# audio.net
KiCad netlist of a schematic drawn in Altium Designer
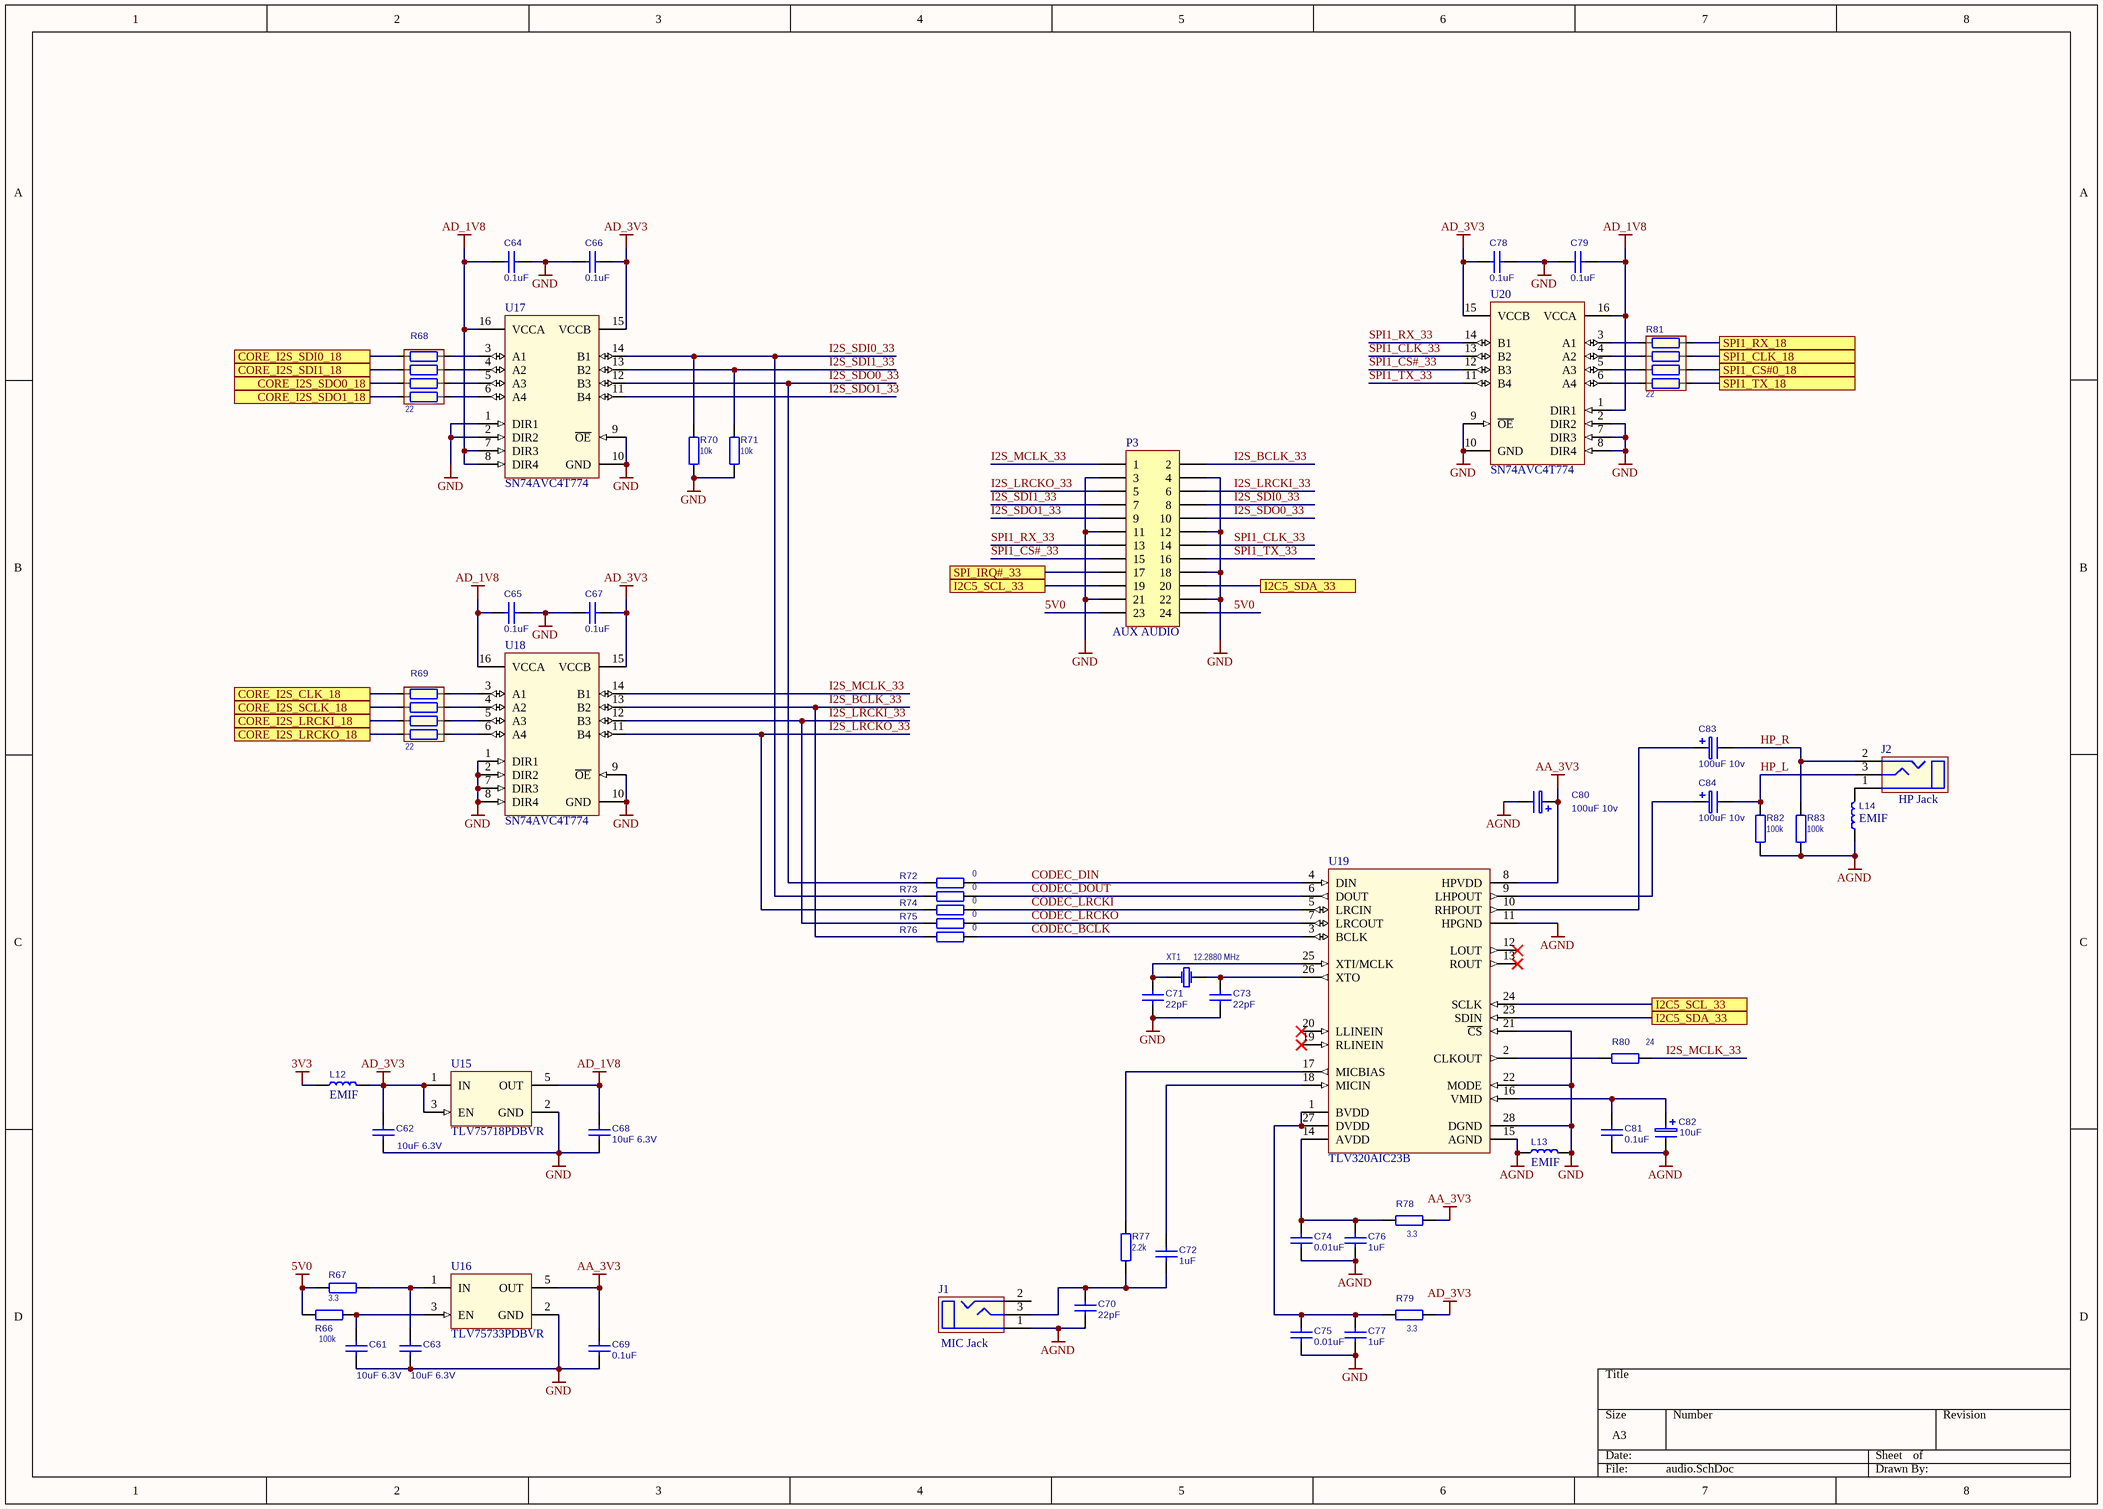
[diagram p0: audio.SchDoc]

(export (version "E")
  (design (tool "Eeschema 10.0.6"))
  (components
    (comp (ref "C61")
      (value "10uF 6.3V")
      (footprint "Capacitors:C0603")
      (description "CAP_NPOL")
      (fields (field (name "Comment") "CC0603MRX5R5BB106"))
      (libsource (lib "capacitors") (part "CAP_NPOL"))
    )
    (comp (ref "C62")
      (value "10uF 6.3V")
      (footprint "Capacitors:C0603")
      (description "CAP_NPOL")
      (fields (field (name "Comment") "CC0603MRX5R5BB106"))
      (libsource (lib "capacitors") (part "CAP_NPOL"))
    )
    (comp (ref "C63")
      (value "10uF 6.3V")
      (footprint "Capacitors:C0603")
      (description "CAP_NPOL")
      (fields (field (name "Comment") "CC0603MRX5R5BB106"))
      (libsource (lib "capacitors") (part "CAP_NPOL"))
    )
    (comp (ref "C64")
      (value "0.1uF")
      (footprint "Capacitors:C0603")
      (description "CAP_NPOL")
      (fields (field (name "Comment") "C1608X7R1H104K080AA"))
      (libsource (lib "capacitors") (part "CAP_NPOL"))
    )
    (comp (ref "C65")
      (value "0.1uF")
      (footprint "Capacitors:C0603")
      (description "CAP_NPOL")
      (fields (field (name "Comment") "C1608X7R1H104K080AA"))
      (libsource (lib "capacitors") (part "CAP_NPOL"))
    )
    (comp (ref "C66")
      (value "0.1uF")
      (footprint "Capacitors:C0603")
      (description "CAP_NPOL")
      (fields (field (name "Comment") "C1608X7R1H104K080AA"))
      (libsource (lib "capacitors") (part "CAP_NPOL"))
    )
    (comp (ref "C67")
      (value "0.1uF")
      (footprint "Capacitors:C0603")
      (description "CAP_NPOL")
      (fields (field (name "Comment") "C1608X7R1H104K080AA"))
      (libsource (lib "capacitors") (part "CAP_NPOL"))
    )
    (comp (ref "C68")
      (value "10uF 6.3V")
      (footprint "Capacitors:C0603")
      (description "CAP_NPOL")
      (fields (field (name "Comment") "CC0603MRX5R5BB106"))
      (libsource (lib "capacitors") (part "CAP_NPOL"))
    )
    (comp (ref "C69")
      (value "0.1uF")
      (footprint "Capacitors:C0603")
      (description "CAP_NPOL")
      (fields (field (name "Comment") "C1608X7R1H104K080AA"))
      (libsource (lib "capacitors") (part "CAP_NPOL"))
    )
    (comp (ref "C70")
      (value "22pF")
      (footprint "C0603")
      (description "CAP_NPOL")
      (libsource (lib "capacitors") (part "CAP_NPOL"))
    )
    (comp (ref "C71")
      (value "22pF")
      (footprint "Capacitors:C0603")
      (description "CAP_NPOL")
      (libsource (lib "capacitors") (part "CAP_NPOL"))
    )
    (comp (ref "C72")
      (value "1uF")
      (footprint "Capacitors:C0603")
      (description "CAP_NPOL")
      (fields (field (name "Comment") "GRM188R61H105KAALD"))
      (libsource (lib "capacitors") (part "CAP_NPOL"))
    )
    (comp (ref "C73")
      (value "22pF")
      (footprint "Capacitors:C0603")
      (description "CAP_NPOL")
      (libsource (lib "capacitors") (part "CAP_NPOL"))
    )
    (comp (ref "C74")
      (value "0.01uF")
      (footprint "Capacitors:C0603")
      (description "CAP_NPOL")
      (fields (field (name "Comment") "C1608X7R1H104K080AA"))
      (libsource (lib "capacitors") (part "CAP_NPOL"))
    )
    (comp (ref "C75")
      (value "0.01uF")
      (footprint "Capacitors:C0603")
      (description "CAP_NPOL")
      (fields (field (name "Comment") "C1608X7R1H104K080AA"))
      (libsource (lib "capacitors") (part "CAP_NPOL"))
    )
    (comp (ref "C76")
      (value "1uF")
      (footprint "Capacitors:C0603")
      (description "CAP_NPOL")
      (fields (field (name "Comment") "GRM188R61H105KAALD"))
      (libsource (lib "capacitors") (part "CAP_NPOL"))
    )
    (comp (ref "C77")
      (value "1uF")
      (footprint "Capacitors:C0603")
      (description "CAP_NPOL")
      (fields (field (name "Comment") "GRM188R61H105KAALD"))
      (libsource (lib "capacitors") (part "CAP_NPOL"))
    )
    (comp (ref "C78")
      (value "0.1uF")
      (footprint "Capacitors:C0603")
      (description "CAP_NPOL")
      (fields (field (name "Comment") "C1608X7R1H104K080AA"))
      (libsource (lib "capacitors") (part "CAP_NPOL"))
    )
    (comp (ref "C79")
      (value "0.1uF")
      (footprint "Capacitors:C0603")
      (description "CAP_NPOL")
      (fields (field (name "Comment") "C1608X7R1H104K080AA"))
      (libsource (lib "capacitors") (part "CAP_NPOL"))
    )
    (comp (ref "C80")
      (value "100uF 10v")
      (footprint "Capacitors:R06H11")
      (description "CAP_POL")
      (fields (field (name "Comment") "SH010M0100B2F-0511"))
      (libsource (lib "capacitors") (part "CAP_POL"))
    )
    (comp (ref "C81")
      (value "0.1uF")
      (footprint "Capacitors:C0603")
      (description "CAP_NPOL")
      (fields (field (name "Comment") "C1608X7R1H104K080AA"))
      (libsource (lib "capacitors") (part "CAP_NPOL"))
    )
    (comp (ref "C82")
      (value "10uF")
      (footprint "Capacitors:TANTAL-A-1206")
      (description "CAP_POL")
      (libsource (lib "capacitors") (part "CAP_POL"))
    )
    (comp (ref "C83")
      (value "100uF 10v")
      (footprint "Capacitors:R06H11")
      (description "CAP_POL")
      (fields (field (name "Comment") "SH010M0100B2F-0511"))
      (libsource (lib "capacitors") (part "CAP_POL"))
    )
    (comp (ref "C84")
      (value "100uF 10v")
      (footprint "Capacitors:R06H11")
      (description "CAP_POL")
      (fields (field (name "Comment") "SH010M0100B2F-0511"))
      (libsource (lib "capacitors") (part "CAP_POL"))
    )
    (comp (ref "J1")
      (value "MIC Jack")
      (footprint "AUB-13")
      (description "Phonejack Stereo")
      (fields (field (name "Comment") "AUB-13"))
      (libsource (lib "PhoneJack") (part "PhoneJackStereo"))
    )
    (comp (ref "J2")
      (value "HP Jack")
      (footprint "AUB-13")
      (description "Phonejack Stereo")
      (fields (field (name "Comment") "AUB-13"))
      (libsource (lib "") (part "PhoneJackStereo_1"))
    )
    (comp (ref "L12")
      (value "EMIF")
      (footprint "IND0805")
      (description "IND_WO_IRON")
      (fields (field (name "Comment") "BLM21PG221SN1D"))
      (libsource (lib "inductors") (part "IND_WO_IRON"))
    )
    (comp (ref "L13")
      (value "EMIF")
      (footprint "IND0805")
      (description "IND_WO_IRON")
      (fields (field (name "Comment") "BLM21PG221SN1D"))
      (libsource (lib "inductors") (part "IND_WO_IRON"))
    )
    (comp (ref "L14")
      (value "EMIF")
      (footprint "IND0805")
      (description "IND_WO_IRON")
      (fields (field (name "Comment") "BLM21PG221SN1D"))
      (libsource (lib "inductors") (part "IND_WO_IRON"))
    )
    (comp (ref "P3")
      (value "AUX AUDIO")
      (footprint "PLD-12")
      (description "Header, 12-Pin, Dual row")
      (fields (field (name "PUBLISHER") "Altium Limited"))
      (libsource (lib "HDR") (part "HDR 12X2"))
    )
    (comp (ref "R66")
      (value "100k")
      (footprint "R0603")
      (description "RES")
      (libsource (lib "resistors") (part "RESISTOR"))
    )
    (comp (ref "R67")
      (value "3.3")
      (footprint "R1206")
      (description "RES")
      (libsource (lib "resistors") (part "RESISTOR"))
    )
    (comp (ref "R68")
      (value "22")
      (footprint "Resistors:R0804X4")
      (description "ARRAY")
      (fields (field (name "Comment") "TC124-JR-0722RL"))
      (libsource (lib "resistors") (part "ARRAY"))
    )
    (comp (ref "R69")
      (value "22")
      (footprint "Resistors:R0804X4")
      (description "ARRAY")
      (fields (field (name "Comment") "TC124-JR-0722RL"))
      (libsource (lib "resistors") (part "ARRAY"))
    )
    (comp (ref "R70")
      (value "10k")
      (footprint "R0603")
      (description "RES")
      (libsource (lib "resistors") (part "RESISTOR"))
    )
    (comp (ref "R71")
      (value "10k")
      (footprint "R0603")
      (description "RES")
      (libsource (lib "resistors") (part "RESISTOR"))
    )
    (comp (ref "R72")
      (value "0")
      (footprint "R0603")
      (description "RES")
      (libsource (lib "resistors") (part "RESISTOR"))
    )
    (comp (ref "R73")
      (value "0")
      (footprint "R0603")
      (description "RES")
      (libsource (lib "resistors") (part "RESISTOR"))
    )
    (comp (ref "R74")
      (value "0")
      (footprint "R0603")
      (description "RES")
      (libsource (lib "resistors") (part "RESISTOR"))
    )
    (comp (ref "R75")
      (value "0")
      (footprint "R0603")
      (description "RES")
      (libsource (lib "resistors") (part "RESISTOR"))
    )
    (comp (ref "R76")
      (value "0")
      (footprint "R0603")
      (description "RES")
      (libsource (lib "resistors") (part "RESISTOR"))
    )
    (comp (ref "R77")
      (value "2.2k")
      (footprint "R0603")
      (description "RES")
      (libsource (lib "resistors") (part "RESISTOR"))
    )
    (comp (ref "R78")
      (value "3.3")
      (footprint "R1206")
      (description "RES")
      (libsource (lib "resistors") (part "RESISTOR"))
    )
    (comp (ref "R79")
      (value "3.3")
      (footprint "R1206")
      (description "RES")
      (libsource (lib "resistors") (part "RESISTOR"))
    )
    (comp (ref "R80")
      (value "24")
      (footprint "R0603")
      (description "RES")
      (fields (field (name "Comment") "22"))
      (libsource (lib "resistors") (part "RESISTOR"))
    )
    (comp (ref "R81")
      (value "22")
      (footprint "Resistors:R0804X4")
      (description "ARRAY")
      (fields (field (name "Comment") "TC124-JR-0722RL"))
      (libsource (lib "") (part "ARRAY_1"))
    )
    (comp (ref "R82")
      (value "100k")
      (footprint "R0603")
      (description "RES")
      (libsource (lib "resistors") (part "RESISTOR"))
    )
    (comp (ref "R83")
      (value "100k")
      (footprint "R0603")
      (description "RES")
      (libsource (lib "resistors") (part "RESISTOR"))
    )
    (comp (ref "U15")
      (value "TLV75718PDBVR")
      (footprint "SOT-23-5")
      (description "Capacitor-Free, 300-mA, Low-Dropout Regulator with Foldback Current Limit for Portable Devices")
      (libsource (lib "TLV733P") (part "TLV733P"))
    )
    (comp (ref "U16")
      (value "TLV75733PDBVR")
      (footprint "SOT-23-5")
      (description "Capacitor-Free, 300-mA, Low-Dropout Regulator with Foldback Current Limit for Portable Devices")
      (libsource (lib "TLV733P") (part "TLV733P"))
    )
    (comp (ref "U17")
      (value "SN74AVC4T774")
      (footprint "TSSOP-16")
      (description "4-Bit Dual-Supply Bus Transceiver With Configurable Voltage-Level Shifting and 3-State Outputs")
      (libsource (lib "SN74AVC4T774") (part "SN74AVC4T774"))
    )
    (comp (ref "U18")
      (value "SN74AVC4T774")
      (footprint "TSSOP-16")
      (description "4-Bit Dual-Supply Bus Transceiver With Configurable Voltage-Level Shifting and 3-State Outputs")
      (libsource (lib "SN74AVC4T774") (part "SN74AVC4T774"))
    )
    (comp (ref "U19")
      (value "TLV320AIC23B")
      (footprint "TSSOP-28")
      (description "Stereo Audio CODEC")
      (libsource (lib "TLV320AIC23") (part "TLV320AIC23"))
    )
    (comp (ref "U20")
      (value "SN74AVC4T774")
      (footprint "TSSOP-16")
      (description "4-Bit Dual-Supply Bus Transceiver With Configurable Voltage-Level Shifting and 3-State Outputs")
      (libsource (lib "") (part "SN74AVC4T774_1"))
    )
    (comp (ref "XT1")
      (value "12.2880 MHz")
      (footprint "HC-49/S")
      (description "Xtal")
      (fields (field (name "Comment") "KX-3H 12.2880 MHz"))
      (libsource (lib "xtal") (part "XTAL"))
    )
  )
  (nets
    (net (code "1") (name "/CODEC_BCLK") (class "Default")
      (node (ref "R76") (pin "2") (pinfunction "2_2") (pintype "passive"))
      (node (ref "U19") (pin "3") (pinfunction "BCLK_3") (pintype "bidirectional"))
    )
    (net (code "2") (name "/CODEC_DIN") (class "Default")
      (node (ref "R72") (pin "2") (pinfunction "2_2") (pintype "passive"))
      (node (ref "U19") (pin "4") (pinfunction "DIN_4") (pintype "input"))
    )
    (net (code "3") (name "/CODEC_DOUT") (class "Default")
      (node (ref "R73") (pin "2") (pinfunction "2_2") (pintype "passive"))
      (node (ref "U19") (pin "6") (pinfunction "DOUT_6") (pintype "output"))
    )
    (net (code "4") (name "/CODEC_LRCKI") (class "Default")
      (node (ref "R74") (pin "2") (pinfunction "2_2") (pintype "passive"))
      (node (ref "U19") (pin "5") (pinfunction "LRCIN_5") (pintype "bidirectional"))
    )
    (net (code "5") (name "/CODEC_LRCKO") (class "Default")
      (node (ref "R75") (pin "2") (pinfunction "2_2") (pintype "passive"))
      (node (ref "U19") (pin "7") (pinfunction "LRCOUT_7") (pintype "bidirectional"))
    )
    (net (code "6") (name "/CORE_I2S_CLK_18") (class "Default")
      (node (ref "R69") (pin "1") (pinfunction "1_1") (pintype "passive"))
    )
    (net (code "7") (name "/CORE_I2S_LRCKI_18") (class "Default")
      (node (ref "R69") (pin "5") (pinfunction "5_5") (pintype "passive"))
    )
    (net (code "8") (name "/CORE_I2S_LRCKO_18") (class "Default")
      (node (ref "R69") (pin "7") (pinfunction "7_7") (pintype "passive"))
    )
    (net (code "9") (name "/CORE_I2S_SCLK_18") (class "Default")
      (node (ref "R69") (pin "3") (pinfunction "3_3") (pintype "passive"))
    )
    (net (code "10") (name "/CORE_I2S_SDI0_18") (class "Default")
      (node (ref "R68") (pin "1") (pinfunction "1_1") (pintype "passive"))
    )
    (net (code "11") (name "/CORE_I2S_SDI1_18") (class "Default")
      (node (ref "R68") (pin "3") (pinfunction "3_3") (pintype "passive"))
    )
    (net (code "12") (name "/CORE_I2S_SDO0_18") (class "Default")
      (node (ref "R68") (pin "5") (pinfunction "5_5") (pintype "passive"))
    )
    (net (code "13") (name "/CORE_I2S_SDO1_18") (class "Default")
      (node (ref "R68") (pin "7") (pinfunction "7_7") (pintype "passive"))
    )
    (net (code "14") (name "/HP_L") (class "Default")
      (node (ref "C84") (pin "2") (pinfunction "-_2") (pintype "passive"))
      (node (ref "J2") (pin "3") (pinfunction "L_3") (pintype "passive"))
      (node (ref "R82") (pin "1") (pinfunction "1_1") (pintype "passive"))
    )
    (net (code "15") (name "/HP_R") (class "Default")
      (node (ref "C83") (pin "2") (pinfunction "-_2") (pintype "passive"))
      (node (ref "J2") (pin "2") (pinfunction "R_2") (pintype "passive"))
      (node (ref "R83") (pin "1") (pinfunction "1_1") (pintype "passive"))
    )
    (net (code "16") (name "/I2C5_SCL_33") (class "Default")
      (node (ref "P3") (pin "19") (pinfunction "19_19") (pintype "passive"))
      (node (ref "U19") (pin "24") (pinfunction "SCLK_24") (pintype "input"))
    )
    (net (code "17") (name "/I2C5_SDA_33") (class "Default")
      (node (ref "P3") (pin "20") (pinfunction "20_20") (pintype "passive"))
      (node (ref "U19") (pin "23") (pinfunction "SDIN_23") (pintype "input"))
    )
    (net (code "18") (name "/I2S_BCLK_33") (class "Default")
      (node (ref "P3") (pin "2") (pinfunction "2_2") (pintype "passive"))
      (node (ref "R76") (pin "1") (pinfunction "1_1") (pintype "passive"))
      (node (ref "U18") (pin "13") (pinfunction "B2_13") (pintype "bidirectional"))
    )
    (net (code "19") (name "/I2S_LRCKI_33") (class "Default")
      (node (ref "P3") (pin "6") (pinfunction "6_6") (pintype "passive"))
      (node (ref "R75") (pin "1") (pinfunction "1_1") (pintype "passive"))
      (node (ref "U18") (pin "12") (pinfunction "B3_12") (pintype "bidirectional"))
    )
    (net (code "20") (name "/I2S_LRCKO_33") (class "Default")
      (node (ref "P3") (pin "5") (pinfunction "5_5") (pintype "passive"))
      (node (ref "R74") (pin "1") (pinfunction "1_1") (pintype "passive"))
      (node (ref "U18") (pin "11") (pinfunction "B4_11") (pintype "bidirectional"))
    )
    (net (code "21") (name "/I2S_MCLK_33") (class "Default")
      (node (ref "P3") (pin "1") (pinfunction "1_1") (pintype "passive"))
      (node (ref "R80") (pin "1") (pinfunction "1_1") (pintype "passive"))
      (node (ref "U18") (pin "14") (pinfunction "B1_14") (pintype "bidirectional"))
    )
    (net (code "22") (name "/I2S_SDI0_33") (class "Default")
      (node (ref "P3") (pin "8") (pinfunction "8_8") (pintype "passive"))
      (node (ref "R70") (pin "1") (pinfunction "1_1") (pintype "passive"))
      (node (ref "R73") (pin "1") (pinfunction "1_1") (pintype "passive"))
      (node (ref "U17") (pin "14") (pinfunction "B1_14") (pintype "bidirectional"))
    )
    (net (code "23") (name "/I2S_SDI1_33") (class "Default")
      (node (ref "P3") (pin "7") (pinfunction "7_7") (pintype "passive"))
      (node (ref "R71") (pin "1") (pinfunction "1_1") (pintype "passive"))
      (node (ref "U17") (pin "13") (pinfunction "B2_13") (pintype "bidirectional"))
    )
    (net (code "24") (name "/I2S_SDO0_33") (class "Default")
      (node (ref "P3") (pin "10") (pinfunction "10_10") (pintype "passive"))
      (node (ref "R72") (pin "1") (pinfunction "1_1") (pintype "passive"))
      (node (ref "U17") (pin "12") (pinfunction "B3_12") (pintype "bidirectional"))
    )
    (net (code "25") (name "/I2S_SDO1_33") (class "Default")
      (node (ref "P3") (pin "9") (pinfunction "9_9") (pintype "passive"))
      (node (ref "U17") (pin "11") (pinfunction "B4_11") (pintype "bidirectional"))
    )
    (net (code "26") (name "/SPI1_CLK_18") (class "Default")
      (node (ref "R81") (pin "3") (pinfunction "3_3") (pintype "passive"))
    )
    (net (code "27") (name "/SPI1_CLK_33") (class "Default")
      (node (ref "P3") (pin "14") (pinfunction "14_14") (pintype "passive"))
      (node (ref "U20") (pin "13") (pinfunction "B2_13") (pintype "bidirectional"))
    )
    (net (code "28") (name "/SPI1_CS#0_18") (class "Default")
      (node (ref "R81") (pin "5") (pinfunction "5_5") (pintype "passive"))
    )
    (net (code "29") (name "/SPI1_CS#_33") (class "Default")
      (node (ref "P3") (pin "15") (pinfunction "15_15") (pintype "passive"))
      (node (ref "U20") (pin "12") (pinfunction "B3_12") (pintype "bidirectional"))
    )
    (net (code "30") (name "/SPI1_RX_18") (class "Default")
      (node (ref "R81") (pin "1") (pinfunction "1_1") (pintype "passive"))
    )
    (net (code "31") (name "/SPI1_RX_33") (class "Default")
      (node (ref "P3") (pin "13") (pinfunction "13_13") (pintype "passive"))
      (node (ref "U20") (pin "14") (pinfunction "B1_14") (pintype "bidirectional"))
    )
    (net (code "32") (name "/SPI1_TX_18") (class "Default")
      (node (ref "R81") (pin "7") (pinfunction "7_7") (pintype "passive"))
    )
    (net (code "33") (name "/SPI1_TX_33") (class "Default")
      (node (ref "P3") (pin "16") (pinfunction "16_16") (pintype "passive"))
      (node (ref "U20") (pin "11") (pinfunction "B4_11") (pintype "bidirectional"))
    )
    (net (code "34") (name "/SPI_IRQ#_33") (class "Default")
      (node (ref "P3") (pin "17") (pinfunction "17_17") (pintype "passive"))
    )
    (net (code "35") (name "3V3") (class "Default") (node (ref "L12") (pin "2") (pintype "passive")))
    (net (code "36") (name "5V0") (class "Default")
      (node (ref "P3") (pin "23") (pinfunction "23_23") (pintype "passive"))
      (node (ref "P3") (pin "24") (pinfunction "24_24") (pintype "passive"))
      (node (ref "R66") (pin "1") (pinfunction "1_1") (pintype "passive"))
      (node (ref "R67") (pin "2") (pinfunction "2_2") (pintype "passive"))
    )
    (net (code "37") (name "AA_3V3") (class "Default")
      (node (ref "C69") (pin "1") (pinfunction "1_1") (pintype "passive"))
      (node (ref "C80") (pin "1") (pinfunction "+_1") (pintype "passive"))
      (node (ref "R78") (pin "1") (pinfunction "1_1") (pintype "passive"))
      (node (ref "U16") (pin "5") (pinfunction "OUT_5") (pintype "power_in"))
      (node (ref "U19") (pin "8") (pinfunction "HPVDD_8") (pintype "power_in"))
    )
    (net (code "38") (name "AD_1V8") (class "Default")
      (node (ref "C64") (pin "2") (pinfunction "2_2") (pintype "passive"))
      (node (ref "C65") (pin "2") (pinfunction "2_2") (pintype "passive"))
      (node (ref "C68") (pin "1") (pinfunction "1_1") (pintype "passive"))
      (node (ref "C79") (pin "2") (pinfunction "2_2") (pintype "passive"))
      (node (ref "U15") (pin "5") (pinfunction "OUT_5") (pintype "power_in"))
      (node (ref "U17") (pin "16") (pinfunction "VCCA_16") (pintype "power_in"))
      (node (ref "U17") (pin "7") (pinfunction "DIR3_7") (pintype "input"))
      (node (ref "U17") (pin "8") (pinfunction "DIR4_8") (pintype "input"))
      (node (ref "U18") (pin "16") (pinfunction "VCCA_16") (pintype "power_in"))
      (node (ref "U20") (pin "1") (pinfunction "DIR1_1") (pintype "input"))
      (node (ref "U20") (pin "16") (pinfunction "VCCA_16") (pintype "power_in"))
    )
    (net (code "39") (name "AD_3V3") (class "Default")
      (node (ref "C62") (pin "1") (pinfunction "1_1") (pintype "passive"))
      (node (ref "C66") (pin "1") (pinfunction "1_1") (pintype "passive"))
      (node (ref "C67") (pin "1") (pinfunction "1_1") (pintype "passive"))
      (node (ref "C78") (pin "1") (pinfunction "1_1") (pintype "passive"))
      (node (ref "L12") (pin "1") (pintype "passive"))
      (node (ref "R79") (pin "1") (pinfunction "1_1") (pintype "passive"))
      (node (ref "U15") (pin "1") (pinfunction "IN_1") (pintype "power_in"))
      (node (ref "U15") (pin "3") (pinfunction "EN_3") (pintype "input"))
      (node (ref "U17") (pin "15") (pinfunction "VCCB_15") (pintype "power_in"))
      (node (ref "U18") (pin "15") (pinfunction "VCCB_15") (pintype "power_in"))
      (node (ref "U20") (pin "15") (pinfunction "VCCB_15") (pintype "power_in"))
    )
    (net (code "40") (name "AGND") (class "Default")
      (node (ref "C70") (pin "2") (pinfunction "2_2") (pintype "passive"))
      (node (ref "C74") (pin "2") (pinfunction "2_2") (pintype "passive"))
      (node (ref "C76") (pin "1") (pinfunction "1_1") (pintype "passive"))
      (node (ref "C80") (pin "2") (pinfunction "-_2") (pintype "passive"))
      (node (ref "C81") (pin "2") (pinfunction "2_2") (pintype "passive"))
      (node (ref "C82") (pin "2") (pinfunction "-_2") (pintype "passive"))
      (node (ref "J1") (pin "1") (pinfunction "C_1") (pintype "passive"))
      (node (ref "L13") (pin "2") (pintype "passive"))
      (node (ref "L14") (pin "2") (pintype "passive"))
      (node (ref "R82") (pin "2") (pinfunction "2_2") (pintype "passive"))
      (node (ref "R83") (pin "2") (pinfunction "2_2") (pintype "passive"))
      (node (ref "U19") (pin "11") (pinfunction "HPGND_11") (pintype "power_in"))
      (node (ref "U19") (pin "15") (pinfunction "AGND_15") (pintype "power_in"))
    )
    (net (code "41") (name "GND") (class "Default")
      (node (ref "C61") (pin "2") (pinfunction "2_2") (pintype "passive"))
      (node (ref "C62") (pin "2") (pinfunction "2_2") (pintype "passive"))
      (node (ref "C63") (pin "2") (pinfunction "2_2") (pintype "passive"))
      (node (ref "C64") (pin "1") (pinfunction "1_1") (pintype "passive"))
      (node (ref "C65") (pin "1") (pinfunction "1_1") (pintype "passive"))
      (node (ref "C66") (pin "2") (pinfunction "2_2") (pintype "passive"))
      (node (ref "C67") (pin "2") (pinfunction "2_2") (pintype "passive"))
      (node (ref "C68") (pin "2") (pinfunction "2_2") (pintype "passive"))
      (node (ref "C69") (pin "2") (pinfunction "2_2") (pintype "passive"))
      (node (ref "C71") (pin "1") (pinfunction "1_1") (pintype "passive"))
      (node (ref "C73") (pin "1") (pinfunction "1_1") (pintype "passive"))
      (node (ref "C75") (pin "2") (pinfunction "2_2") (pintype "passive"))
      (node (ref "C77") (pin "1") (pinfunction "1_1") (pintype "passive"))
      (node (ref "C78") (pin "2") (pinfunction "2_2") (pintype "passive"))
      (node (ref "C79") (pin "1") (pinfunction "1_1") (pintype "passive"))
      (node (ref "L13") (pin "1") (pintype "passive"))
      (node (ref "P3") (pin "11") (pinfunction "11_11") (pintype "passive"))
      (node (ref "P3") (pin "12") (pinfunction "12_12") (pintype "passive"))
      (node (ref "P3") (pin "18") (pinfunction "18_18") (pintype "passive"))
      (node (ref "P3") (pin "21") (pinfunction "21_21") (pintype "passive"))
      (node (ref "P3") (pin "22") (pinfunction "22_22") (pintype "passive"))
      (node (ref "P3") (pin "3") (pinfunction "3_3") (pintype "passive"))
      (node (ref "P3") (pin "4") (pinfunction "4_4") (pintype "passive"))
      (node (ref "R70") (pin "2") (pinfunction "2_2") (pintype "passive"))
      (node (ref "R71") (pin "2") (pinfunction "2_2") (pintype "passive"))
      (node (ref "U15") (pin "2") (pinfunction "GND_2") (pintype "power_in"))
      (node (ref "U16") (pin "2") (pinfunction "GND_2") (pintype "power_in"))
      (node (ref "U17") (pin "1") (pinfunction "DIR1_1") (pintype "input"))
      (node (ref "U17") (pin "10") (pinfunction "GND_10") (pintype "power_in"))
      (node (ref "U17") (pin "2") (pinfunction "DIR2_2") (pintype "input"))
      (node (ref "U17") (pin "9") (pinfunction "~{OE}_9") (pintype "input"))
      (node (ref "U18") (pin "1") (pinfunction "DIR1_1") (pintype "input"))
      (node (ref "U18") (pin "10") (pinfunction "GND_10") (pintype "power_in"))
      (node (ref "U18") (pin "2") (pinfunction "DIR2_2") (pintype "input"))
      (node (ref "U18") (pin "7") (pinfunction "DIR3_7") (pintype "input"))
      (node (ref "U18") (pin "8") (pinfunction "DIR4_8") (pintype "input"))
      (node (ref "U18") (pin "9") (pinfunction "~{OE}_9") (pintype "input"))
      (node (ref "U19") (pin "21") (pinfunction "~{CS}_21") (pintype "input"))
      (node (ref "U19") (pin "22") (pinfunction "MODE_22") (pintype "input"))
      (node (ref "U19") (pin "28") (pinfunction "DGND_28") (pintype "passive"))
      (node (ref "U20") (pin "10") (pinfunction "GND_10") (pintype "power_in"))
      (node (ref "U20") (pin "2") (pinfunction "DIR2_2") (pintype "input"))
      (node (ref "U20") (pin "7") (pinfunction "DIR3_7") (pintype "input"))
      (node (ref "U20") (pin "8") (pinfunction "DIR4_8") (pintype "input"))
      (node (ref "U20") (pin "9") (pinfunction "~{OE}_9") (pintype "input"))
    )
    (net (code "42") (name "Net-(C82-+)") (class "Default")
      (node (ref "C81") (pin "1") (pinfunction "1_1") (pintype "passive"))
      (node (ref "C82") (pin "1") (pinfunction "+_1") (pintype "passive"))
      (node (ref "U19") (pin "16") (pinfunction "VMID_16") (pintype "input"))
    )
    (net (code "43") (name "Net-(C83-+)") (class "Default")
      (node (ref "C83") (pin "1") (pinfunction "+_1") (pintype "passive"))
      (node (ref "U19") (pin "10") (pinfunction "RHPOUT_10") (pintype "output"))
    )
    (net (code "44") (name "Net-(C84-+)") (class "Default")
      (node (ref "C84") (pin "1") (pinfunction "+_1") (pintype "passive"))
      (node (ref "U19") (pin "9") (pinfunction "LHPOUT_9") (pintype "output"))
    )
    (net (code "45") (name "Net-(J1-L)") (class "Default")
      (node (ref "C70") (pin "1") (pinfunction "1_1") (pintype "passive"))
      (node (ref "C72") (pin "2") (pinfunction "2_2") (pintype "passive"))
      (node (ref "J1") (pin "3") (pinfunction "L_3") (pintype "passive"))
      (node (ref "R77") (pin "2") (pinfunction "2_2") (pintype "passive"))
    )
    (net (code "46") (name "Net-(J2-C)") (class "Default")
      (node (ref "J2") (pin "1") (pinfunction "C_1") (pintype "passive"))
      (node (ref "L14") (pin "1") (pintype "passive"))
    )
    (net (code "47") (name "Net-(U16-EN)") (class "Default")
      (node (ref "C61") (pin "1") (pinfunction "1_1") (pintype "passive"))
      (node (ref "R66") (pin "2") (pinfunction "2_2") (pintype "passive"))
      (node (ref "U16") (pin "3") (pinfunction "EN_3") (pintype "input"))
    )
    (net (code "48") (name "Net-(U16-IN)") (class "Default")
      (node (ref "C63") (pin "1") (pinfunction "1_1") (pintype "passive"))
      (node (ref "R67") (pin "1") (pinfunction "1_1") (pintype "passive"))
      (node (ref "U16") (pin "1") (pinfunction "IN_1") (pintype "power_in"))
    )
    (net (code "49") (name "Net-(U17-A1)") (class "Default")
      (node (ref "R68") (pin "2") (pinfunction "2_2") (pintype "passive"))
      (node (ref "U17") (pin "3") (pinfunction "A1_3") (pintype "bidirectional"))
    )
    (net (code "50") (name "Net-(U17-A2)") (class "Default")
      (node (ref "R68") (pin "4") (pinfunction "4_4") (pintype "passive"))
      (node (ref "U17") (pin "4") (pinfunction "A2_4") (pintype "bidirectional"))
    )
    (net (code "51") (name "Net-(U17-A3)") (class "Default")
      (node (ref "R68") (pin "6") (pinfunction "6_6") (pintype "passive"))
      (node (ref "U17") (pin "5") (pinfunction "A3_5") (pintype "bidirectional"))
    )
    (net (code "52") (name "Net-(U17-A4)") (class "Default")
      (node (ref "R68") (pin "8") (pinfunction "8_8") (pintype "passive"))
      (node (ref "U17") (pin "6") (pinfunction "A4_6") (pintype "bidirectional"))
    )
    (net (code "53") (name "Net-(U18-A1)") (class "Default")
      (node (ref "R69") (pin "2") (pinfunction "2_2") (pintype "passive"))
      (node (ref "U18") (pin "3") (pinfunction "A1_3") (pintype "bidirectional"))
    )
    (net (code "54") (name "Net-(U18-A2)") (class "Default")
      (node (ref "R69") (pin "4") (pinfunction "4_4") (pintype "passive"))
      (node (ref "U18") (pin "4") (pinfunction "A2_4") (pintype "bidirectional"))
    )
    (net (code "55") (name "Net-(U18-A3)") (class "Default")
      (node (ref "R69") (pin "6") (pinfunction "6_6") (pintype "passive"))
      (node (ref "U18") (pin "5") (pinfunction "A3_5") (pintype "bidirectional"))
    )
    (net (code "56") (name "Net-(U18-A4)") (class "Default")
      (node (ref "R69") (pin "8") (pinfunction "8_8") (pintype "passive"))
      (node (ref "U18") (pin "6") (pinfunction "A4_6") (pintype "bidirectional"))
    )
    (net (code "57") (name "Net-(U19-AVDD)") (class "Default")
      (node (ref "C74") (pin "1") (pinfunction "1_1") (pintype "passive"))
      (node (ref "C76") (pin "2") (pinfunction "2_2") (pintype "passive"))
      (node (ref "R78") (pin "2") (pinfunction "2_2") (pintype "passive"))
      (node (ref "U19") (pin "14") (pinfunction "AVDD_14") (pintype "power_in"))
    )
    (net (code "58") (name "Net-(U19-BVDD)") (class "Default")
      (node (ref "C75") (pin "1") (pinfunction "1_1") (pintype "passive"))
      (node (ref "C77") (pin "2") (pinfunction "2_2") (pintype "passive"))
      (node (ref "R79") (pin "2") (pinfunction "2_2") (pintype "passive"))
      (node (ref "U19") (pin "1") (pinfunction "BVDD_1") (pintype "power_in"))
      (node (ref "U19") (pin "27") (pinfunction "DVDD_27") (pintype "power_in"))
    )
    (net (code "59") (name "Net-(U19-CLKOUT)") (class "Default")
      (node (ref "R80") (pin "2") (pinfunction "2_2") (pintype "passive"))
      (node (ref "U19") (pin "2") (pinfunction "CLKOUT_2") (pintype "output"))
    )
    (net (code "60") (name "Net-(U19-MICBIAS)") (class "Default")
      (node (ref "R77") (pin "1") (pinfunction "1_1") (pintype "passive"))
      (node (ref "U19") (pin "17") (pinfunction "MICBIAS_17") (pintype "output"))
    )
    (net (code "61") (name "Net-(U19-MICIN)") (class "Default")
      (node (ref "C72") (pin "1") (pinfunction "1_1") (pintype "passive"))
      (node (ref "U19") (pin "18") (pinfunction "MICIN_18") (pintype "input"))
    )
    (net (code "62") (name "Net-(U19-XTI{slash}MCLK)") (class "Default")
      (node (ref "C71") (pin "2") (pinfunction "2_2") (pintype "passive"))
      (node (ref "U19") (pin "25") (pinfunction "XTI/MCLK_25") (pintype "input"))
      (node (ref "XT1") (pin "1") (pintype "passive"))
    )
    (net (code "63") (name "Net-(U19-XTO)") (class "Default")
      (node (ref "C73") (pin "2") (pinfunction "2_2") (pintype "passive"))
      (node (ref "U19") (pin "26") (pinfunction "XTO_26") (pintype "output"))
      (node (ref "XT1") (pin "2") (pintype "passive"))
    )
    (net (code "64") (name "Net-(U20-A1)") (class "Default")
      (node (ref "R81") (pin "2") (pinfunction "2_2") (pintype "passive"))
      (node (ref "U20") (pin "3") (pinfunction "A1_3") (pintype "bidirectional"))
    )
    (net (code "65") (name "Net-(U20-A2)") (class "Default")
      (node (ref "R81") (pin "4") (pinfunction "4_4") (pintype "passive"))
      (node (ref "U20") (pin "4") (pinfunction "A2_4") (pintype "bidirectional"))
    )
    (net (code "66") (name "Net-(U20-A3)") (class "Default")
      (node (ref "R81") (pin "6") (pinfunction "6_6") (pintype "passive"))
      (node (ref "U20") (pin "5") (pinfunction "A3_5") (pintype "bidirectional"))
    )
    (net (code "67") (name "Net-(U20-A4)") (class "Default")
      (node (ref "R81") (pin "8") (pinfunction "8_8") (pintype "passive"))
      (node (ref "U20") (pin "6") (pinfunction "A4_6") (pintype "bidirectional"))
    )
    (net (code "68") (name "unconnected-(J1-R-Pad2)") (class "Default")
      (node (ref "J1") (pin "2") (pinfunction "R_2") (pintype "passive"))
    )
    (net (code "69") (name "unconnected-(U19-LLINEIN-Pad20)") (class "Default")
      (node (ref "U19") (pin "20") (pinfunction "LLINEIN_20") (pintype "input+no_connect"))
    )
    (net (code "70") (name "unconnected-(U19-LOUT-Pad12)") (class "Default")
      (node (ref "U19") (pin "12") (pinfunction "LOUT_12") (pintype "output+no_connect"))
    )
    (net (code "71") (name "unconnected-(U19-RLINEIN-Pad19)") (class "Default")
      (node (ref "U19") (pin "19") (pinfunction "RLINEIN_19") (pintype "input+no_connect"))
    )
    (net (code "72") (name "unconnected-(U19-ROUT-Pad13)") (class "Default")
      (node (ref "U19") (pin "13") (pinfunction "ROUT_13") (pintype "output+no_connect"))
    )
  )
)
